# 472kHz-Transverter.net
KiCad netlist of a schematic drawn in EAGLE
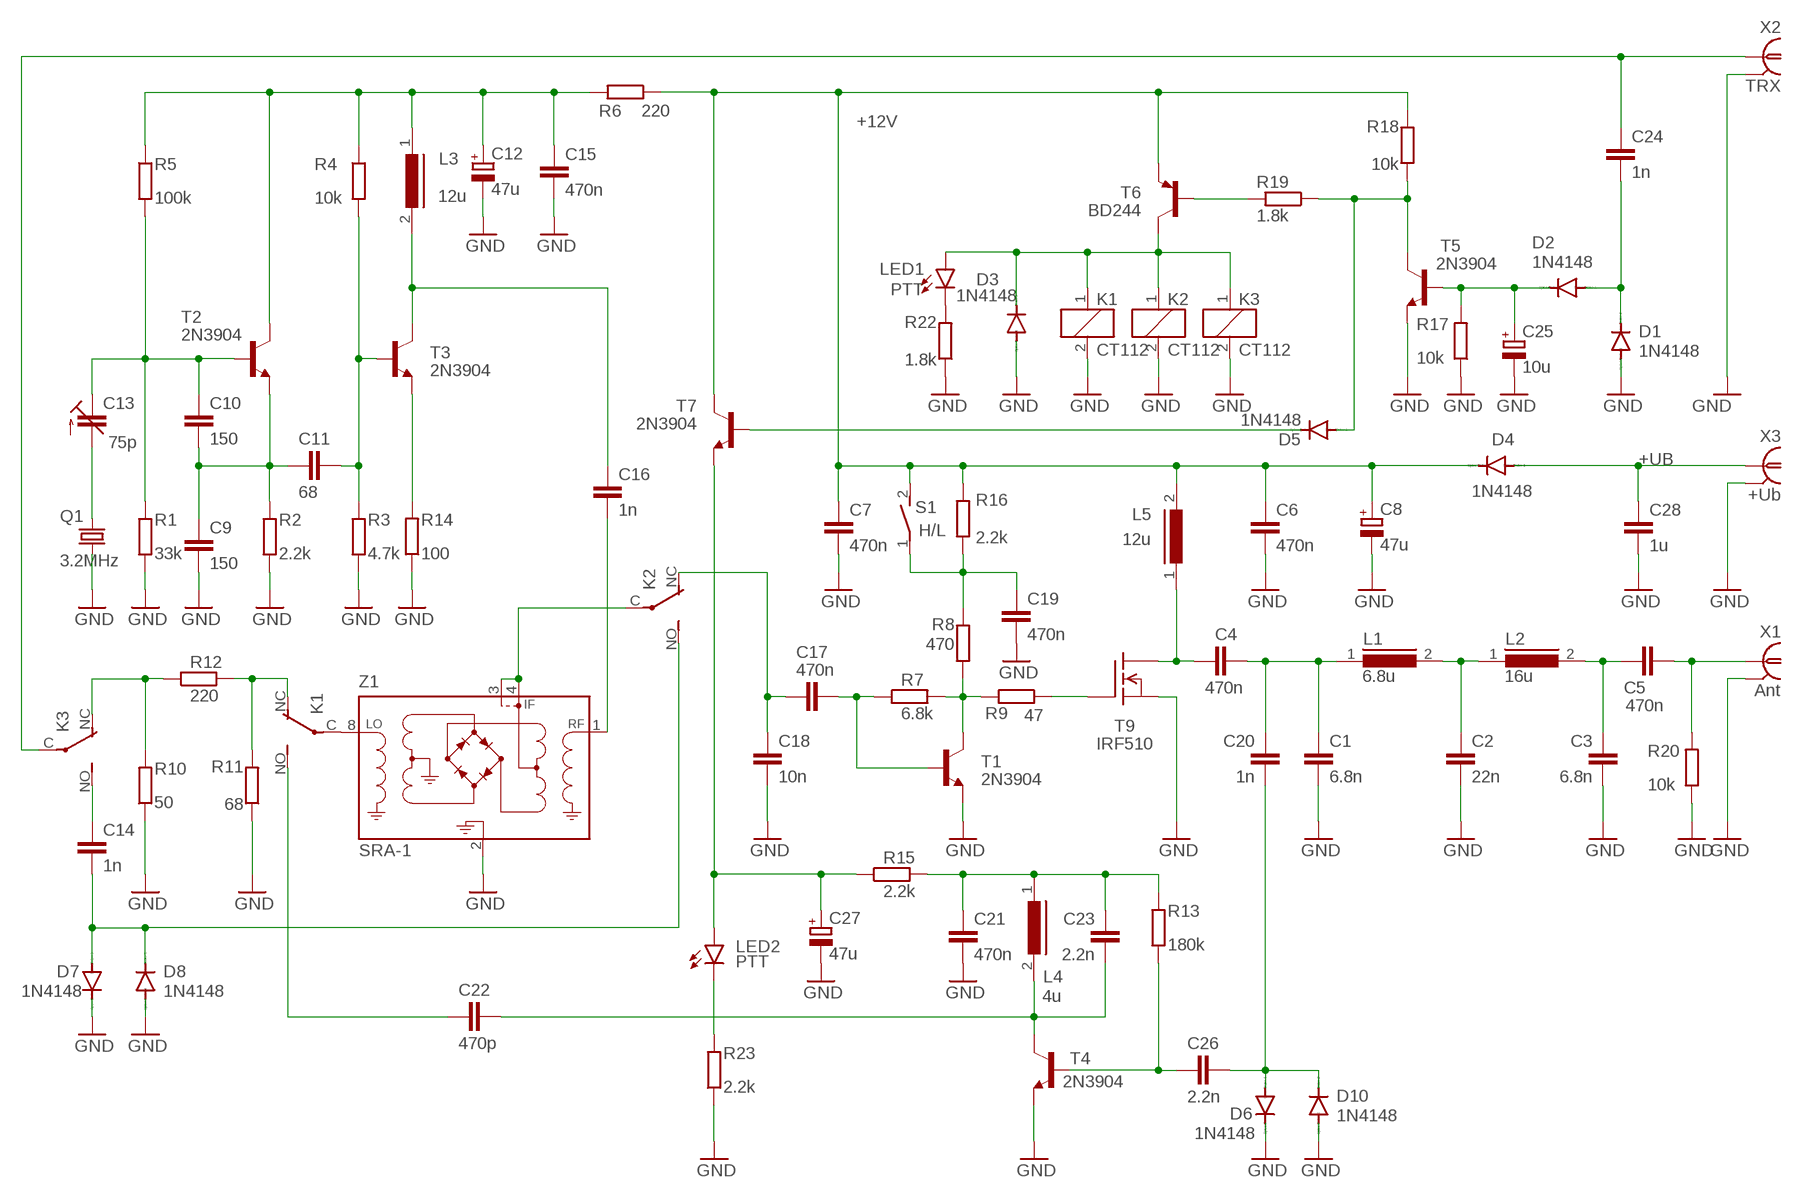
[diagram p0: schematic, sheet 1]

(export (version "E")
  (design (tool "Eeschema 10.0.6"))
  (components
    (comp (ref "C1")
      (value "6.8n")
      (footprint "eagle-import:C5B2.5")
      (libsource (lib "eagle-import") (part "C5/2.5"))
    )
    (comp (ref "C2")
      (value "22n")
      (footprint "eagle-import:C5B2.5")
      (libsource (lib "eagle-import") (part "C5/2.5"))
    )
    (comp (ref "C3")
      (value "6.8n")
      (footprint "eagle-import:C5B2.5")
      (libsource (lib "eagle-import") (part "C5/2.5"))
    )
    (comp (ref "C4")
      (value "470n")
      (footprint "eagle-import:C5B2.5")
      (libsource (lib "eagle-import") (part "C5/2.5"))
    )
    (comp (ref "C5")
      (value "470n")
      (footprint "eagle-import:C5B2.5")
      (libsource (lib "eagle-import") (part "C5/2.5"))
    )
    (comp (ref "C6")
      (value "470n")
      (footprint "eagle-import:C5B2.5")
      (libsource (lib "eagle-import") (part "C5/2.5"))
    )
    (comp (ref "C7")
      (value "470n")
      (footprint "eagle-import:C5B2.5")
      (libsource (lib "eagle-import") (part "C5/2.5"))
    )
    (comp (ref "C8")
      (value "47u")
      (footprint "eagle-import:CT7343")
      (libsource (lib "eagle-import") (part "CPOL-EUCT7343"))
    )
    (comp (ref "C9")
      (value "150")
      (footprint "eagle-import:C5B2.5")
      (libsource (lib "eagle-import") (part "C5/2.5"))
    )
    (comp (ref "C10")
      (value "150")
      (footprint "eagle-import:C5B2.5")
      (libsource (lib "eagle-import") (part "C5/2.5"))
    )
    (comp (ref "C11")
      (value "68")
      (footprint "eagle-import:C5B2.5")
      (libsource (lib "eagle-import") (part "C5/2.5"))
    )
    (comp (ref "C12")
      (value "47u")
      (footprint "eagle-import:CT7343")
      (libsource (lib "eagle-import") (part "CPOL-EUCT7343"))
    )
    (comp (ref "C13")
      (value "75p")
      (footprint "eagle-import:CTRIM808-1")
      (libsource (lib "eagle-import") (part "C-TRIMM808-1"))
    )
    (comp (ref "C14")
      (value "1n")
      (footprint "eagle-import:C5B2.5")
      (libsource (lib "eagle-import") (part "C5/2.5"))
    )
    (comp (ref "C15")
      (value "470n")
      (footprint "eagle-import:C5B2.5")
      (libsource (lib "eagle-import") (part "C5/2.5"))
    )
    (comp (ref "C16")
      (value "1n")
      (footprint "eagle-import:C5B2.5")
      (libsource (lib "eagle-import") (part "C5/2.5"))
    )
    (comp (ref "C17")
      (value "470n")
      (footprint "eagle-import:C5B2.5")
      (libsource (lib "eagle-import") (part "C5/2.5"))
    )
    (comp (ref "C18")
      (value "10n")
      (footprint "eagle-import:C5B2.5")
      (libsource (lib "eagle-import") (part "C5/2.5"))
    )
    (comp (ref "C19")
      (value "470n")
      (footprint "eagle-import:C5B2.5")
      (libsource (lib "eagle-import") (part "C5/2.5"))
    )
    (comp (ref "C20")
      (value "1n")
      (footprint "eagle-import:C5B2.5")
      (libsource (lib "eagle-import") (part "C5/2.5"))
    )
    (comp (ref "C21")
      (value "470n")
      (footprint "eagle-import:C5B2.5")
      (libsource (lib "eagle-import") (part "C5/2.5"))
    )
    (comp (ref "C22")
      (value "470p")
      (footprint "eagle-import:C5B2.5")
      (libsource (lib "eagle-import") (part "C5/2.5"))
    )
    (comp (ref "C23")
      (value "2.2n")
      (footprint "eagle-import:C5B2.5")
      (libsource (lib "eagle-import") (part "C5/2.5"))
    )
    (comp (ref "C24")
      (value "1n")
      (footprint "eagle-import:C5B2.5")
      (libsource (lib "eagle-import") (part "C5/2.5"))
    )
    (comp (ref "C25")
      (value "10u")
      (footprint "eagle-import:CT7343")
      (libsource (lib "eagle-import") (part "CPOL-EUCT7343"))
    )
    (comp (ref "C26")
      (value "2.2n")
      (footprint "eagle-import:C5B2.5")
      (libsource (lib "eagle-import") (part "C5/2.5"))
    )
    (comp (ref "C27")
      (value "47u")
      (footprint "eagle-import:CT7343")
      (libsource (lib "eagle-import") (part "CPOL-EUCT7343"))
    )
    (comp (ref "C28")
      (value "1u")
      (footprint "eagle-import:C5B2.5")
      (libsource (lib "eagle-import") (part "C5/2.5"))
    )
    (comp (ref "D1")
      (value "1N4148")
      (footprint "eagle-import:DO35-7")
      (libsource (lib "eagle-import") (part "1N4148DO35-7"))
    )
    (comp (ref "D2")
      (value "1N4148")
      (footprint "eagle-import:DO35-7")
      (libsource (lib "eagle-import") (part "1N4148DO35-7"))
    )
    (comp (ref "D3")
      (value "1N4148")
      (footprint "eagle-import:DO35-7")
      (libsource (lib "eagle-import") (part "1N4148DO35-7"))
    )
    (comp (ref "D4")
      (value "1N4148")
      (footprint "eagle-import:DO35-7")
      (libsource (lib "eagle-import") (part "1N4148DO35-7"))
    )
    (comp (ref "D5")
      (value "1N4148")
      (footprint "eagle-import:DO35-7")
      (libsource (lib "eagle-import") (part "1N4148DO35-7"))
    )
    (comp (ref "D6")
      (value "1N4148")
      (footprint "eagle-import:DO35-7")
      (libsource (lib "eagle-import") (part "1N4148DO35-7"))
    )
    (comp (ref "D7")
      (value "1N4148")
      (footprint "eagle-import:DO35-7")
      (libsource (lib "eagle-import") (part "1N4148DO35-7"))
    )
    (comp (ref "D8")
      (value "1N4148")
      (footprint "eagle-import:DO35-7")
      (libsource (lib "eagle-import") (part "1N4148DO35-7"))
    )
    (comp (ref "D10")
      (value "1N4148")
      (footprint "eagle-import:DO35-7")
      (libsource (lib "eagle-import") (part "1N4148DO35-7"))
    )
    (comp (ref "K1")
      (value "CT112")
      (footprint "eagle-import:CT-SLIM")
      (libsource (lib "eagle-import") (part "CT112"))
    )
    (comp (ref "K2")
      (value "CT112")
      (footprint "eagle-import:CT-SLIM")
      (libsource (lib "eagle-import") (part "CT112"))
    )
    (comp (ref "K3")
      (value "CT112")
      (footprint "eagle-import:CT-SLIM")
      (libsource (lib "eagle-import") (part "CT112"))
    )
    (comp (ref "L1")
      (value "6.8u")
      (footprint "eagle-import:ED22")
      (libsource (lib "eagle-import") (part "ED22"))
    )
    (comp (ref "L2")
      (value "16u")
      (footprint "eagle-import:ED22")
      (libsource (lib "eagle-import") (part "ED22"))
    )
    (comp (ref "L3")
      (value "12u")
      (footprint "eagle-import:ED22")
      (libsource (lib "eagle-import") (part "ED22"))
    )
    (comp (ref "L4")
      (value "4u")
      (footprint "eagle-import:ED22")
      (libsource (lib "eagle-import") (part "ED22"))
    )
    (comp (ref "L5")
      (value "12u")
      (footprint "eagle-import:ED22")
      (libsource (lib "eagle-import") (part "ED22"))
    )
    (comp (ref "LED1")
      (value "PTT")
      (footprint "eagle-import:W57B")
      (libsource (lib "eagle-import") (part "W57BLA"))
    )
    (comp (ref "LED2")
      (value "PTT")
      (footprint "eagle-import:W57B")
      (libsource (lib "eagle-import") (part "W57BLA"))
    )
    (comp (ref "Q1")
      (value "3.2MHz")
      (footprint "eagle-import:11.4X4.5")
      (libsource (lib "eagle-import") (part "KX-KS"))
    )
    (comp (ref "R1")
      (value "33k")
      (footprint "eagle-import:0207_5V")
      (libsource (lib "eagle-import") (part "R-EU_0207/5V"))
    )
    (comp (ref "R2")
      (value "2.2k")
      (footprint "eagle-import:0207_5V")
      (libsource (lib "eagle-import") (part "R-EU_0207/5V"))
    )
    (comp (ref "R3")
      (value "4.7k")
      (footprint "eagle-import:0207_5V")
      (libsource (lib "eagle-import") (part "R-EU_0207/5V"))
    )
    (comp (ref "R4")
      (value "10k")
      (footprint "eagle-import:0207_5V")
      (libsource (lib "eagle-import") (part "R-EU_0207/5V"))
    )
    (comp (ref "R5")
      (value "100k")
      (footprint "eagle-import:0207_5V")
      (libsource (lib "eagle-import") (part "R-EU_0207/5V"))
    )
    (comp (ref "R6")
      (value "220")
      (footprint "eagle-import:0207_5V")
      (libsource (lib "eagle-import") (part "R-EU_0207/5V"))
    )
    (comp (ref "R7")
      (value "6.8k")
      (footprint "eagle-import:0207_5V")
      (libsource (lib "eagle-import") (part "R-EU_0207/5V"))
    )
    (comp (ref "R8")
      (value "470")
      (footprint "eagle-import:0207_5V")
      (libsource (lib "eagle-import") (part "R-EU_0207/5V"))
    )
    (comp (ref "R9")
      (value "47")
      (footprint "eagle-import:0207_5V")
      (libsource (lib "eagle-import") (part "R-EU_0207/5V"))
    )
    (comp (ref "R10")
      (value "50")
      (footprint "eagle-import:0207_5V")
      (libsource (lib "eagle-import") (part "R-EU_0207/5V"))
    )
    (comp (ref "R11")
      (value "68")
      (footprint "eagle-import:0207_5V")
      (libsource (lib "eagle-import") (part "R-EU_0207/5V"))
    )
    (comp (ref "R12")
      (value "220")
      (footprint "eagle-import:0207_5V")
      (libsource (lib "eagle-import") (part "R-EU_0207/5V"))
    )
    (comp (ref "R13")
      (value "180k")
      (footprint "eagle-import:0207_5V")
      (libsource (lib "eagle-import") (part "R-EU_0207/5V"))
    )
    (comp (ref "R14")
      (value "100")
      (footprint "eagle-import:0207_5V")
      (libsource (lib "eagle-import") (part "R-EU_0207/5V"))
    )
    (comp (ref "R15")
      (value "2.2k")
      (footprint "eagle-import:0207_5V")
      (libsource (lib "eagle-import") (part "R-EU_0207/5V"))
    )
    (comp (ref "R16")
      (value "2.2k")
      (footprint "eagle-import:0207_5V")
      (libsource (lib "eagle-import") (part "R-EU_0207/5V"))
    )
    (comp (ref "R17")
      (value "10k")
      (footprint "eagle-import:0207_5V")
      (libsource (lib "eagle-import") (part "R-EU_0207/5V"))
    )
    (comp (ref "R18")
      (value "10k")
      (footprint "eagle-import:0207_5V")
      (libsource (lib "eagle-import") (part "R-EU_0207/5V"))
    )
    (comp (ref "R19")
      (value "1.8k")
      (footprint "eagle-import:0207_5V")
      (libsource (lib "eagle-import") (part "R-EU_0207/5V"))
    )
    (comp (ref "R20")
      (value "10k")
      (footprint "eagle-import:0207_5V")
      (libsource (lib "eagle-import") (part "R-EU_0207/5V"))
    )
    (comp (ref "R22")
      (value "1.8k")
      (footprint "eagle-import:0207_5V")
      (libsource (lib "eagle-import") (part "R-EU_0207/5V"))
    )
    (comp (ref "R23")
      (value "2.2k")
      (footprint "eagle-import:0207_5V")
      (libsource (lib "eagle-import") (part "R-EU_0207/5V"))
    )
    (comp (ref "S1")
      (value "H/L")
      (footprint "eagle-import:DS-01")
      (libsource (lib "eagle-import") (part "DS01E"))
    )
    (comp (ref "T1")
      (value "2N3904")
      (footprint "eagle-import:TO92")
      (libsource (lib "eagle-import") (part "2N3904"))
    )
    (comp (ref "T2")
      (value "2N3904")
      (footprint "eagle-import:TO92")
      (libsource (lib "eagle-import") (part "2N3904"))
    )
    (comp (ref "T3")
      (value "2N3904")
      (footprint "eagle-import:TO92")
      (libsource (lib "eagle-import") (part "2N3904"))
    )
    (comp (ref "T4")
      (value "2N3904")
      (footprint "eagle-import:TO92")
      (libsource (lib "eagle-import") (part "2N3904"))
    )
    (comp (ref "T5")
      (value "2N3904")
      (footprint "eagle-import:TO92")
      (libsource (lib "eagle-import") (part "2N3904"))
    )
    (comp (ref "T6")
      (value "BD244")
      (footprint "eagle-import:TO220")
      (libsource (lib "eagle-import") (part "BD244"))
    )
    (comp (ref "T7")
      (value "2N3904")
      (footprint "eagle-import:TO92")
      (libsource (lib "eagle-import") (part "2N3904"))
    )
    (comp (ref "T9")
      (value "IRF510")
      (footprint "eagle-import:TO220")
      (libsource (lib "eagle-import") (part "IRF510"))
    )
    (comp (ref "X1")
      (value "Ant")
      (footprint "eagle-import:R141426")
      (fields (field (name "MF") "FARNELL") (field (name "MPN") "R141426161"))
      (libsource (lib "eagle-import") (part "R141426"))
    )
    (comp (ref "X2")
      (value "TRX")
      (footprint "eagle-import:R141426")
      (fields (field (name "MF") "FARNELL") (field (name "MPN") "R141426161"))
      (libsource (lib "eagle-import") (part "R141426"))
    )
    (comp (ref "X3")
      (value "+Ub")
      (footprint "eagle-import:R141426")
      (fields (field (name "MF") "FARNELL") (field (name "MPN") "R141426161"))
      (libsource (lib "eagle-import") (part "R141426"))
    )
    (comp (ref "Z1")
      (value "SRA-1")
      (footprint "eagle-import:A01")
      (libsource (lib "eagle-import") (part "SRA-1"))
    )
  )
  (nets
    (net (code "1") (name "/+12V") (class "Default")
      (node (ref "C6") (pin "1") (pinfunction "1_1") (pintype "passive"))
      (node (ref "C7") (pin "1") (pinfunction "1_1") (pintype "passive"))
      (node (ref "C8") (pin "+") (pinfunction "+_+") (pintype "passive"))
      (node (ref "D4") (pin "C") (pinfunction "C_C") (pintype "passive"))
      (node (ref "L5") (pin "2") (pinfunction "2_2") (pintype "passive"))
      (node (ref "R16") (pin "2") (pinfunction "2_2") (pintype "passive"))
      (node (ref "R18") (pin "2") (pinfunction "2_2") (pintype "passive"))
      (node (ref "R6") (pin "1") (pinfunction "1_1") (pintype "passive"))
      (node (ref "S1") (pin "2") (pinfunction "2_2") (pintype "passive"))
      (node (ref "T6") (pin "3") (pinfunction "E_3") (pintype "passive"))
      (node (ref "T7") (pin "1") (pinfunction "C_1") (pintype "passive"))
    )
    (net (code "2") (name "/+UB") (class "Default")
      (node (ref "C28") (pin "1") (pinfunction "1_1") (pintype "passive"))
      (node (ref "D4") (pin "A") (pinfunction "A_A") (pintype "passive"))
      (node (ref "X3") (pin "1") (pinfunction "1_1") (pintype "passive"))
    )
    (net (code "3") (name "GND") (class "Default")
      (node (ref "C1") (pin "2") (pinfunction "2_2") (pintype "passive"))
      (node (ref "C12") (pin "-") (pinfunction "-_-") (pintype "passive"))
      (node (ref "C15") (pin "2") (pinfunction "2_2") (pintype "passive"))
      (node (ref "C18") (pin "2") (pinfunction "2_2") (pintype "passive"))
      (node (ref "C19") (pin "2") (pinfunction "2_2") (pintype "passive"))
      (node (ref "C2") (pin "2") (pinfunction "2_2") (pintype "passive"))
      (node (ref "C21") (pin "2") (pinfunction "2_2") (pintype "passive"))
      (node (ref "C25") (pin "-") (pinfunction "-_-") (pintype "passive"))
      (node (ref "C27") (pin "-") (pinfunction "-_-") (pintype "passive"))
      (node (ref "C28") (pin "2") (pinfunction "2_2") (pintype "passive"))
      (node (ref "C3") (pin "2") (pinfunction "2_2") (pintype "passive"))
      (node (ref "C6") (pin "2") (pinfunction "2_2") (pintype "passive"))
      (node (ref "C7") (pin "2") (pinfunction "2_2") (pintype "passive"))
      (node (ref "C8") (pin "-") (pinfunction "-_-") (pintype "passive"))
      (node (ref "C9") (pin "2") (pinfunction "2_2") (pintype "passive"))
      (node (ref "D1") (pin "A") (pinfunction "A_A") (pintype "passive"))
      (node (ref "D10") (pin "A") (pinfunction "A_A") (pintype "passive"))
      (node (ref "D3") (pin "A") (pinfunction "A_A") (pintype "passive"))
      (node (ref "D6") (pin "C") (pinfunction "C_C") (pintype "passive"))
      (node (ref "D7") (pin "C") (pinfunction "C_C") (pintype "passive"))
      (node (ref "D8") (pin "A") (pinfunction "A_A") (pintype "passive"))
      (node (ref "K1") (pin "2") (pinfunction "2_2") (pintype "passive"))
      (node (ref "K2") (pin "2") (pinfunction "2_2") (pintype "passive"))
      (node (ref "K3") (pin "2") (pinfunction "2_2") (pintype "passive"))
      (node (ref "Q1") (pin "2") (pinfunction "2_2") (pintype "passive"))
      (node (ref "R1") (pin "2") (pinfunction "2_2") (pintype "passive"))
      (node (ref "R10") (pin "1") (pinfunction "1_1") (pintype "passive"))
      (node (ref "R11") (pin "1") (pinfunction "1_1") (pintype "passive"))
      (node (ref "R14") (pin "1") (pinfunction "1_1") (pintype "passive"))
      (node (ref "R17") (pin "1") (pinfunction "1_1") (pintype "passive"))
      (node (ref "R2") (pin "2") (pinfunction "2_2") (pintype "passive"))
      (node (ref "R20") (pin "1") (pinfunction "1_1") (pintype "passive"))
      (node (ref "R22") (pin "1") (pinfunction "1_1") (pintype "passive"))
      (node (ref "R23") (pin "1") (pinfunction "1_1") (pintype "passive"))
      (node (ref "R3") (pin "2") (pinfunction "2_2") (pintype "passive"))
      (node (ref "T1") (pin "3") (pinfunction "E_3") (pintype "passive"))
      (node (ref "T4") (pin "3") (pinfunction "E_3") (pintype "passive"))
      (node (ref "T5") (pin "3") (pinfunction "E_3") (pintype "passive"))
      (node (ref "T9") (pin "3") (pinfunction "S_3") (pintype "passive"))
      (node (ref "X1") (pin "2") (pinfunction "2_2") (pintype "passive"))
      (node (ref "X1") (pin "3") (pinfunction "2_3") (pintype "passive"))
      (node (ref "X1") (pin "4") (pinfunction "2_4") (pintype "passive"))
      (node (ref "X1") (pin "5") (pinfunction "2_5") (pintype "passive"))
      (node (ref "X2") (pin "2") (pinfunction "2_2") (pintype "passive"))
      (node (ref "X2") (pin "3") (pinfunction "2_3") (pintype "passive"))
      (node (ref "X2") (pin "4") (pinfunction "2_4") (pintype "passive"))
      (node (ref "X2") (pin "5") (pinfunction "2_5") (pintype "passive"))
      (node (ref "X3") (pin "2") (pinfunction "2_2") (pintype "passive"))
      (node (ref "X3") (pin "3") (pinfunction "2_3") (pintype "passive"))
      (node (ref "X3") (pin "4") (pinfunction "2_4") (pintype "passive"))
      (node (ref "X3") (pin "5") (pinfunction "2_5") (pintype "passive"))
      (node (ref "Z1") (pin "2") (pinfunction "CASEGROUND_2") (pintype "passive"))
    )
    (net (code "4") (name "Net-(C1-Pad1)") (class "Default")
      (node (ref "C1") (pin "1") (pinfunction "1_1") (pintype "passive"))
      (node (ref "C20") (pin "2") (pinfunction "2_2") (pintype "passive"))
      (node (ref "C4") (pin "2") (pinfunction "2_2") (pintype "passive"))
      (node (ref "L1") (pin "1") (pinfunction "1_1") (pintype "passive"))
    )
    (net (code "5") (name "Net-(C2-Pad1)") (class "Default")
      (node (ref "C2") (pin "1") (pinfunction "1_1") (pintype "passive"))
      (node (ref "L1") (pin "2") (pinfunction "2_2") (pintype "passive"))
      (node (ref "L2") (pin "1") (pinfunction "1_1") (pintype "passive"))
    )
    (net (code "6") (name "Net-(C3-Pad1)") (class "Default")
      (node (ref "C3") (pin "1") (pinfunction "1_1") (pintype "passive"))
      (node (ref "C5") (pin "1") (pinfunction "1_1") (pintype "passive"))
      (node (ref "L2") (pin "2") (pinfunction "2_2") (pintype "passive"))
    )
    (net (code "7") (name "Net-(C5-Pad2)") (class "Default")
      (node (ref "C5") (pin "2") (pinfunction "2_2") (pintype "passive"))
      (node (ref "R20") (pin "2") (pinfunction "2_2") (pintype "passive"))
      (node (ref "X1") (pin "1") (pinfunction "1_1") (pintype "passive"))
    )
    (net (code "8") (name "Net-(C13-A)") (class "Default")
      (node (ref "C13") (pin "2") (pinfunction "A_2") (pintype "passive"))
      (node (ref "Q1") (pin "1") (pinfunction "1_1") (pintype "passive"))
    )
    (net (code "9") (name "Net-(C13-E)") (class "Default")
      (node (ref "C10") (pin "1") (pinfunction "1_1") (pintype "passive"))
      (node (ref "C13") (pin "1") (pinfunction "E_1") (pintype "passive"))
      (node (ref "R1") (pin "1") (pinfunction "1_1") (pintype "passive"))
      (node (ref "R5") (pin "2") (pinfunction "2_2") (pintype "passive"))
      (node (ref "T2") (pin "2") (pinfunction "B_2") (pintype "passive"))
    )
    (net (code "10") (name "Net-(C19-Pad1)") (class "Default")
      (node (ref "C19") (pin "1") (pinfunction "1_1") (pintype "passive"))
      (node (ref "R16") (pin "1") (pinfunction "1_1") (pintype "passive"))
      (node (ref "R8") (pin "2") (pinfunction "2_2") (pintype "passive"))
      (node (ref "S1") (pin "1") (pinfunction "1_1") (pintype "passive"))
    )
    (net (code "11") (name "Net-(C20-Pad1)") (class "Default")
      (node (ref "C20") (pin "1") (pinfunction "1_1") (pintype "passive"))
      (node (ref "C26") (pin "1") (pinfunction "1_1") (pintype "passive"))
      (node (ref "D10") (pin "C") (pinfunction "C_C") (pintype "passive"))
      (node (ref "D6") (pin "A") (pinfunction "A_A") (pintype "passive"))
    )
    (net (code "12") (name "Net-(C21-Pad1)") (class "Default")
      (node (ref "C21") (pin "1") (pinfunction "1_1") (pintype "passive"))
      (node (ref "C23") (pin "2") (pinfunction "2_2") (pintype "passive"))
      (node (ref "L4") (pin "1") (pinfunction "1_1") (pintype "passive"))
      (node (ref "R13") (pin "2") (pinfunction "2_2") (pintype "passive"))
      (node (ref "R15") (pin "2") (pinfunction "2_2") (pintype "passive"))
    )
    (net (code "13") (name "Net-(C24-Pad2)") (class "Default")
      (node (ref "C24") (pin "2") (pinfunction "2_2") (pintype "passive"))
      (node (ref "D1") (pin "C") (pinfunction "C_C") (pintype "passive"))
      (node (ref "D2") (pin "A") (pinfunction "A_A") (pintype "passive"))
    )
    (net (code "14") (name "Net-(K1B-O)") (class "Default")
      (node (ref "K1") (pin "NC") (pinfunction "O_NC") (pintype "passive"))
      (node (ref "R11") (pin "2") (pinfunction "2_2") (pintype "passive"))
      (node (ref "R12") (pin "2") (pinfunction "2_2") (pintype "passive"))
    )
    (net (code "15") (name "Net-(K1B-P)") (class "Default")
      (node (ref "K1") (pin "C") (pinfunction "P_C") (pintype "passive"))
      (node (ref "Z1") (pin "8") (pinfunction "L_8") (pintype "passive"))
    )
    (net (code "16") (name "Net-(K1B-S)") (class "Default")
      (node (ref "C22") (pin "1") (pinfunction "1_1") (pintype "passive"))
      (node (ref "K1") (pin "NO") (pinfunction "S_NO") (pintype "passive"))
    )
    (net (code "17") (name "Net-(K2B-O)") (class "Default")
      (node (ref "C17") (pin "1") (pinfunction "1_1") (pintype "passive"))
      (node (ref "C18") (pin "1") (pinfunction "1_1") (pintype "passive"))
      (node (ref "K2") (pin "NC") (pinfunction "O_NC") (pintype "passive"))
    )
    (net (code "18") (name "Net-(K2B-P)") (class "Default")
      (node (ref "K2") (pin "C") (pinfunction "P_C") (pintype "passive"))
      (node (ref "Z1") (pin "3") (pinfunction "IF_3") (pintype "passive"))
      (node (ref "Z1") (pin "4") (pinfunction "IF_4") (pintype "passive"))
    )
    (net (code "19") (name "Net-(K2B-S)") (class "Default")
      (node (ref "C14") (pin "2") (pinfunction "2_2") (pintype "passive"))
      (node (ref "D7") (pin "A") (pinfunction "A_A") (pintype "passive"))
      (node (ref "D8") (pin "C") (pinfunction "C_C") (pintype "passive"))
      (node (ref "K2") (pin "NO") (pinfunction "S_NO") (pintype "passive"))
    )
    (net (code "20") (name "Net-(K3B-O)") (class "Default")
      (node (ref "K3") (pin "NC") (pinfunction "O_NC") (pintype "passive"))
      (node (ref "R10") (pin "2") (pinfunction "2_2") (pintype "passive"))
      (node (ref "R12") (pin "1") (pinfunction "1_1") (pintype "passive"))
    )
    (net (code "21") (name "Net-(K3B-P)") (class "Default")
      (node (ref "C24") (pin "1") (pinfunction "1_1") (pintype "passive"))
      (node (ref "K3") (pin "C") (pinfunction "P_C") (pintype "passive"))
      (node (ref "X2") (pin "1") (pinfunction "1_1") (pintype "passive"))
    )
    (net (code "22") (name "Net-(K3B-S)") (class "Default")
      (node (ref "C14") (pin "1") (pinfunction "1_1") (pintype "passive"))
      (node (ref "K3") (pin "NO") (pinfunction "S_NO") (pintype "passive"))
    )
    (net (code "23") (name "Net-(LED1-C-PadC@1)") (class "Default")
      (node (ref "LED1") (pin "C") (pinfunction "C_C") (pintype "passive"))
      (node (ref "LED1") (pin "C@1") (pinfunction "C_C@1") (pintype "passive"))
      (node (ref "LED1") (pin "C@2") (pinfunction "C_C@2") (pintype "passive"))
      (node (ref "LED1") (pin "C@3") (pinfunction "C_C@3") (pintype "passive"))
      (node (ref "LED1") (pin "C@4") (pinfunction "C_C@4") (pintype "passive"))
      (node (ref "LED1") (pin "C@5") (pinfunction "C_C@5") (pintype "passive"))
      (node (ref "R22") (pin "2") (pinfunction "2_2") (pintype "passive"))
    )
    (net (code "24") (name "Net-(LED2-C-PadC@1)") (class "Default")
      (node (ref "LED2") (pin "C") (pinfunction "C_C") (pintype "passive"))
      (node (ref "LED2") (pin "C@1") (pinfunction "C_C@1") (pintype "passive"))
      (node (ref "LED2") (pin "C@2") (pinfunction "C_C@2") (pintype "passive"))
      (node (ref "LED2") (pin "C@3") (pinfunction "C_C@3") (pintype "passive"))
      (node (ref "LED2") (pin "C@4") (pinfunction "C_C@4") (pintype "passive"))
      (node (ref "LED2") (pin "C@5") (pinfunction "C_C@5") (pintype "passive"))
      (node (ref "R23") (pin "2") (pinfunction "2_2") (pintype "passive"))
    )
    (net (code "25") (name "Net-(T1-B)") (class "Default")
      (node (ref "C17") (pin "2") (pinfunction "2_2") (pintype "passive"))
      (node (ref "R7") (pin "1") (pinfunction "1_1") (pintype "passive"))
      (node (ref "T1") (pin "2") (pinfunction "B_2") (pintype "passive"))
    )
    (net (code "26") (name "Net-(T1-C)") (class "Default")
      (node (ref "R7") (pin "2") (pinfunction "2_2") (pintype "passive"))
      (node (ref "R8") (pin "1") (pinfunction "1_1") (pintype "passive"))
      (node (ref "R9") (pin "2") (pinfunction "2_2") (pintype "passive"))
      (node (ref "T1") (pin "1") (pinfunction "C_1") (pintype "passive"))
    )
    (net (code "27") (name "Net-(T2-C)") (class "Default")
      (node (ref "C12") (pin "+") (pinfunction "+_+") (pintype "passive"))
      (node (ref "C15") (pin "1") (pinfunction "1_1") (pintype "passive"))
      (node (ref "L3") (pin "1") (pinfunction "1_1") (pintype "passive"))
      (node (ref "R4") (pin "1") (pinfunction "1_1") (pintype "passive"))
      (node (ref "R5") (pin "1") (pinfunction "1_1") (pintype "passive"))
      (node (ref "R6") (pin "2") (pinfunction "2_2") (pintype "passive"))
      (node (ref "T2") (pin "1") (pinfunction "C_1") (pintype "passive"))
    )
    (net (code "28") (name "Net-(T2-E)") (class "Default")
      (node (ref "C10") (pin "2") (pinfunction "2_2") (pintype "passive"))
      (node (ref "C11") (pin "1") (pinfunction "1_1") (pintype "passive"))
      (node (ref "C9") (pin "1") (pinfunction "1_1") (pintype "passive"))
      (node (ref "R2") (pin "1") (pinfunction "1_1") (pintype "passive"))
      (node (ref "T2") (pin "3") (pinfunction "E_3") (pintype "passive"))
    )
    (net (code "29") (name "Net-(T3-B)") (class "Default")
      (node (ref "C11") (pin "2") (pinfunction "2_2") (pintype "passive"))
      (node (ref "R3") (pin "1") (pinfunction "1_1") (pintype "passive"))
      (node (ref "R4") (pin "2") (pinfunction "2_2") (pintype "passive"))
      (node (ref "T3") (pin "2") (pinfunction "B_2") (pintype "passive"))
    )
    (net (code "30") (name "Net-(T3-C)") (class "Default")
      (node (ref "C16") (pin "1") (pinfunction "1_1") (pintype "passive"))
      (node (ref "L3") (pin "2") (pinfunction "2_2") (pintype "passive"))
      (node (ref "T3") (pin "1") (pinfunction "C_1") (pintype "passive"))
    )
    (net (code "31") (name "Net-(T3-E)") (class "Default")
      (node (ref "R14") (pin "2") (pinfunction "2_2") (pintype "passive"))
      (node (ref "T3") (pin "3") (pinfunction "E_3") (pintype "passive"))
    )
    (net (code "32") (name "Net-(T4-B)") (class "Default")
      (node (ref "C26") (pin "2") (pinfunction "2_2") (pintype "passive"))
      (node (ref "R13") (pin "1") (pinfunction "1_1") (pintype "passive"))
      (node (ref "T4") (pin "2") (pinfunction "B_2") (pintype "passive"))
    )
    (net (code "33") (name "Net-(T4-C)") (class "Default")
      (node (ref "C22") (pin "2") (pinfunction "2_2") (pintype "passive"))
      (node (ref "C23") (pin "1") (pinfunction "1_1") (pintype "passive"))
      (node (ref "L4") (pin "2") (pinfunction "2_2") (pintype "passive"))
      (node (ref "T4") (pin "1") (pinfunction "C_1") (pintype "passive"))
    )
    (net (code "34") (name "Net-(T5-B)") (class "Default")
      (node (ref "C25") (pin "+") (pinfunction "+_+") (pintype "passive"))
      (node (ref "D2") (pin "C") (pinfunction "C_C") (pintype "passive"))
      (node (ref "R17") (pin "2") (pinfunction "2_2") (pintype "passive"))
      (node (ref "T5") (pin "2") (pinfunction "B_2") (pintype "passive"))
    )
    (net (code "35") (name "Net-(T5-C)") (class "Default")
      (node (ref "D5") (pin "A") (pinfunction "A_A") (pintype "passive"))
      (node (ref "R18") (pin "1") (pinfunction "1_1") (pintype "passive"))
      (node (ref "R19") (pin "1") (pinfunction "1_1") (pintype "passive"))
      (node (ref "T5") (pin "1") (pinfunction "C_1") (pintype "passive"))
    )
    (net (code "36") (name "Net-(T6-B)") (class "Default")
      (node (ref "R19") (pin "2") (pinfunction "2_2") (pintype "passive"))
      (node (ref "T6") (pin "1") (pinfunction "B_1") (pintype "passive"))
    )
    (net (code "37") (name "Net-(T6-C)") (class "Default")
      (node (ref "D3") (pin "C") (pinfunction "C_C") (pintype "passive"))
      (node (ref "K1") (pin "1") (pinfunction "1_1") (pintype "passive"))
      (node (ref "K2") (pin "1") (pinfunction "1_1") (pintype "passive"))
      (node (ref "K3") (pin "1") (pinfunction "1_1") (pintype "passive"))
      (node (ref "LED1") (pin "A") (pinfunction "A_A") (pintype "passive"))
      (node (ref "T6") (pin "2") (pinfunction "C_2") (pintype "passive"))
    )
    (net (code "38") (name "Net-(T7-B)") (class "Default")
      (node (ref "D5") (pin "C") (pinfunction "C_C") (pintype "passive"))
      (node (ref "T7") (pin "2") (pinfunction "B_2") (pintype "passive"))
    )
    (net (code "39") (name "Net-(T7-E)") (class "Default")
      (node (ref "C27") (pin "+") (pinfunction "+_+") (pintype "passive"))
      (node (ref "LED2") (pin "A") (pinfunction "A_A") (pintype "passive"))
      (node (ref "R15") (pin "1") (pinfunction "1_1") (pintype "passive"))
      (node (ref "T7") (pin "3") (pinfunction "E_3") (pintype "passive"))
    )
    (net (code "40") (name "Net-(T9-D)") (class "Default")
      (node (ref "C4") (pin "1") (pinfunction "1_1") (pintype "passive"))
      (node (ref "L5") (pin "1") (pinfunction "1_1") (pintype "passive"))
      (node (ref "T9") (pin "2") (pinfunction "D_2") (pintype "passive"))
    )
    (net (code "41") (name "Net-(T9-G)") (class "Default")
      (node (ref "R9") (pin "1") (pinfunction "1_1") (pintype "passive"))
      (node (ref "T9") (pin "1") (pinfunction "G_1") (pintype "passive"))
    )
    (net (code "42") (name "Net-(Z1A-R)") (class "Default")
      (node (ref "C16") (pin "2") (pinfunction "2_2") (pintype "passive"))
      (node (ref "Z1") (pin "1") (pinfunction "R_1") (pintype "passive"))
    )
  )
)
